# Main.net
KiCad netlist of a schematic drawn in Altium Designer
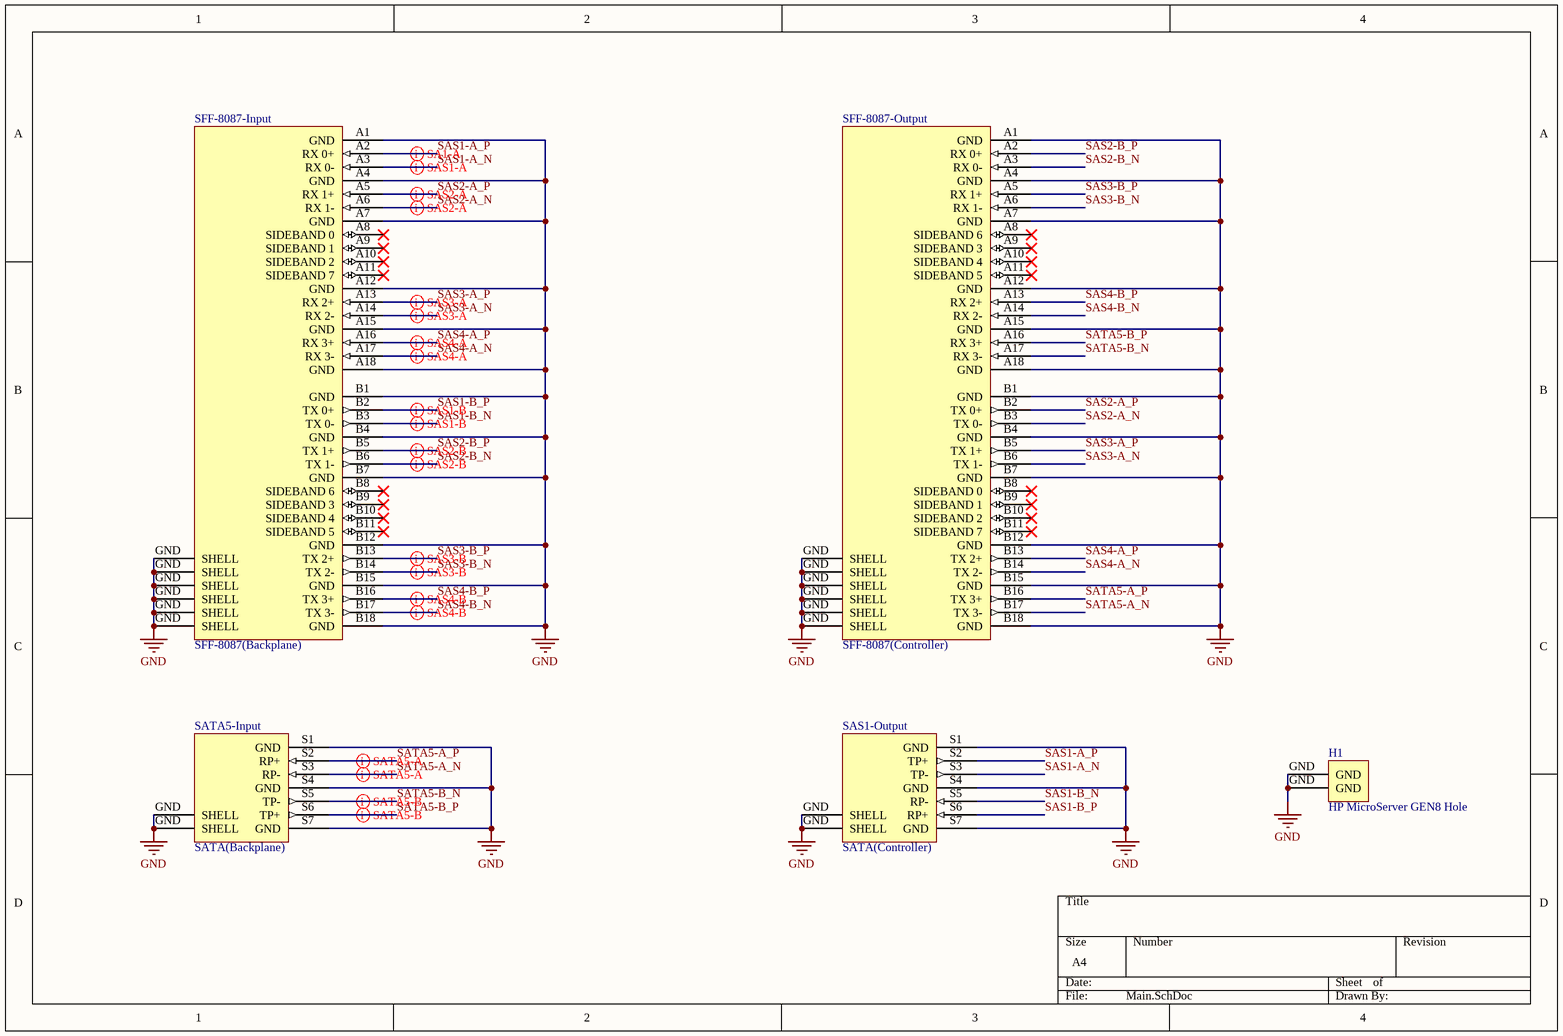
[diagram p0: Main.SchDoc]

(export (version "E")
  (design (tool "Eeschema 10.0.6"))
  (components
    (comp (ref "H1")
      (value "HP MicroServer GEN8 Hole")
      (footprint "GEN8-HDD-Backplane-Hole")
      (libsource (lib "Common") (part "HP MicroServer GEN8 Hole"))
    )
    (comp (ref "SAS1-Output")
      (value "SATA(Controller)")
      (footprint "MOLEX SATA (47080-4001)")
      (libsource (lib "Common") (part "SATA(Controller)"))
    )
    (comp (ref "SATA5-Input")
      (value "SATA(Backplane)")
      (footprint "MOLEX SATA (47080-4001)")
      (libsource (lib "Common") (part "SATA(Backplane)"))
    )
    (comp (ref "SFF-8087-Input")
      (value "SFF-8087(Backplane)")
      (footprint "Molex SFF-8087 (75783-0140)")
      (libsource (lib "Common") (part "SFF-8087(Backplane)"))
    )
    (comp (ref "SFF-8087-Output")
      (value "SFF-8087(Controller)")
      (footprint "Molex SFF-8087 (75783-0140)")
      (libsource (lib "Common") (part "SFF-8087(Controller)"))
    )
  )
  (nets
    (net (code "1") (name "/SAS1-A_N") (class "Default")
      (node (ref "SAS1-Output") (pin "S3") (pinfunction "TP-_S3") (pintype "output"))
      (node (ref "SFF-8087-Input") (pin "A3") (pinfunction "RX_0-_A3") (pintype "input"))
    )
    (net (code "2") (name "/SAS1-A_P") (class "Default")
      (node (ref "SAS1-Output") (pin "S2") (pinfunction "TP+_S2") (pintype "output"))
      (node (ref "SFF-8087-Input") (pin "A2") (pinfunction "RX_0+_A2") (pintype "input"))
    )
    (net (code "3") (name "/SAS1-B_N") (class "Default")
      (node (ref "SAS1-Output") (pin "S5") (pinfunction "RP-_S5") (pintype "input"))
      (node (ref "SFF-8087-Input") (pin "B3") (pinfunction "TX_0-_B3") (pintype "output"))
    )
    (net (code "4") (name "/SAS1-B_P") (class "Default")
      (node (ref "SAS1-Output") (pin "S6") (pinfunction "RP+_S6") (pintype "input"))
      (node (ref "SFF-8087-Input") (pin "B2") (pinfunction "TX_0+_B2") (pintype "output"))
    )
    (net (code "5") (name "/SAS2-A_N") (class "Default")
      (node (ref "SFF-8087-Input") (pin "A6") (pinfunction "RX_1-_A6") (pintype "input"))
      (node (ref "SFF-8087-Output") (pin "B3") (pinfunction "TX_0-_B3") (pintype "output"))
    )
    (net (code "6") (name "/SAS2-A_P") (class "Default")
      (node (ref "SFF-8087-Input") (pin "A5") (pinfunction "RX_1+_A5") (pintype "input"))
      (node (ref "SFF-8087-Output") (pin "B2") (pinfunction "TX_0+_B2") (pintype "output"))
    )
    (net (code "7") (name "/SAS2-B_N") (class "Default")
      (node (ref "SFF-8087-Input") (pin "B6") (pinfunction "TX_1-_B6") (pintype "output"))
      (node (ref "SFF-8087-Output") (pin "A3") (pinfunction "RX_0-_A3") (pintype "input"))
    )
    (net (code "8") (name "/SAS2-B_P") (class "Default")
      (node (ref "SFF-8087-Input") (pin "B5") (pinfunction "TX_1+_B5") (pintype "output"))
      (node (ref "SFF-8087-Output") (pin "A2") (pinfunction "RX_0+_A2") (pintype "input"))
    )
    (net (code "9") (name "/SAS3-A_N") (class "Default")
      (node (ref "SFF-8087-Input") (pin "A14") (pinfunction "RX_2-_A14") (pintype "input"))
      (node (ref "SFF-8087-Output") (pin "B6") (pinfunction "TX_1-_B6") (pintype "output"))
    )
    (net (code "10") (name "/SAS3-A_P") (class "Default")
      (node (ref "SFF-8087-Input") (pin "A13") (pinfunction "RX_2+_A13") (pintype "input"))
      (node (ref "SFF-8087-Output") (pin "B5") (pinfunction "TX_1+_B5") (pintype "output"))
    )
    (net (code "11") (name "/SAS3-B_N") (class "Default")
      (node (ref "SFF-8087-Input") (pin "B14") (pinfunction "TX_2-_B14") (pintype "output"))
      (node (ref "SFF-8087-Output") (pin "A6") (pinfunction "RX_1-_A6") (pintype "input"))
    )
    (net (code "12") (name "/SAS3-B_P") (class "Default")
      (node (ref "SFF-8087-Input") (pin "B13") (pinfunction "TX_2+_B13") (pintype "output"))
      (node (ref "SFF-8087-Output") (pin "A5") (pinfunction "RX_1+_A5") (pintype "input"))
    )
    (net (code "13") (name "/SAS4-A_N") (class "Default")
      (node (ref "SFF-8087-Input") (pin "A17") (pinfunction "RX_3-_A17") (pintype "input"))
      (node (ref "SFF-8087-Output") (pin "B14") (pinfunction "TX_2-_B14") (pintype "output"))
    )
    (net (code "14") (name "/SAS4-A_P") (class "Default")
      (node (ref "SFF-8087-Input") (pin "A16") (pinfunction "RX_3+_A16") (pintype "input"))
      (node (ref "SFF-8087-Output") (pin "B13") (pinfunction "TX_2+_B13") (pintype "output"))
    )
    (net (code "15") (name "/SAS4-B_N") (class "Default")
      (node (ref "SFF-8087-Input") (pin "B17") (pinfunction "TX_3-_B17") (pintype "output"))
      (node (ref "SFF-8087-Output") (pin "A14") (pinfunction "RX_2-_A14") (pintype "input"))
    )
    (net (code "16") (name "/SAS4-B_P") (class "Default")
      (node (ref "SFF-8087-Input") (pin "B16") (pinfunction "TX_3+_B16") (pintype "output"))
      (node (ref "SFF-8087-Output") (pin "A13") (pinfunction "RX_2+_A13") (pintype "input"))
    )
    (net (code "17") (name "/SATA5-A_N") (class "Default")
      (node (ref "SATA5-Input") (pin "S3") (pinfunction "RP-_S3") (pintype "input"))
      (node (ref "SFF-8087-Output") (pin "B17") (pinfunction "TX_3-_B17") (pintype "output"))
    )
    (net (code "18") (name "/SATA5-A_P") (class "Default")
      (node (ref "SATA5-Input") (pin "S2") (pinfunction "RP+_S2") (pintype "input"))
      (node (ref "SFF-8087-Output") (pin "B16") (pinfunction "TX_3+_B16") (pintype "output"))
    )
    (net (code "19") (name "/SATA5-B_N") (class "Default")
      (node (ref "SATA5-Input") (pin "S5") (pinfunction "TP-_S5") (pintype "output"))
      (node (ref "SFF-8087-Output") (pin "A17") (pinfunction "RX_3-_A17") (pintype "input"))
    )
    (net (code "20") (name "/SATA5-B_P") (class "Default")
      (node (ref "SATA5-Input") (pin "S6") (pinfunction "TP+_S6") (pintype "output"))
      (node (ref "SFF-8087-Output") (pin "A16") (pinfunction "RX_3+_A16") (pintype "input"))
    )
    (net (code "21") (name "GND") (class "Default")
      (node (ref "H1") (pin "GND") (pinfunction "GND_GND") (pintype "passive"))
      (node (ref "SAS1-Output") (pin "GND") (pinfunction "SHELL_GND") (pintype "passive"))
      (node (ref "SAS1-Output") (pin "S1") (pinfunction "GND_S1") (pintype "passive"))
      (node (ref "SAS1-Output") (pin "S4") (pinfunction "GND_S4") (pintype "passive"))
      (node (ref "SAS1-Output") (pin "S7") (pinfunction "GND_S7") (pintype "passive"))
      (node (ref "SATA5-Input") (pin "GND") (pinfunction "SHELL_GND") (pintype "passive"))
      (node (ref "SATA5-Input") (pin "S1") (pinfunction "GND_S1") (pintype "passive"))
      (node (ref "SATA5-Input") (pin "S4") (pinfunction "GND_S4") (pintype "passive"))
      (node (ref "SATA5-Input") (pin "S7") (pinfunction "GND_S7") (pintype "passive"))
      (node (ref "SFF-8087-Input") (pin "A1") (pinfunction "GND_A1") (pintype "passive"))
      (node (ref "SFF-8087-Input") (pin "A12") (pinfunction "GND_A12") (pintype "passive"))
      (node (ref "SFF-8087-Input") (pin "A15") (pinfunction "GND_A15") (pintype "passive"))
      (node (ref "SFF-8087-Input") (pin "A18") (pinfunction "GND_A18") (pintype "passive"))
      (node (ref "SFF-8087-Input") (pin "A4") (pinfunction "GND_A4") (pintype "passive"))
      (node (ref "SFF-8087-Input") (pin "A7") (pinfunction "GND_A7") (pintype "passive"))
      (node (ref "SFF-8087-Input") (pin "B1") (pinfunction "GND_B1") (pintype "passive"))
      (node (ref "SFF-8087-Input") (pin "B12") (pinfunction "GND_B12") (pintype "passive"))
      (node (ref "SFF-8087-Input") (pin "B15") (pinfunction "GND_B15") (pintype "passive"))
      (node (ref "SFF-8087-Input") (pin "B18") (pinfunction "GND_B18") (pintype "passive"))
      (node (ref "SFF-8087-Input") (pin "B4") (pinfunction "GND_B4") (pintype "passive"))
      (node (ref "SFF-8087-Input") (pin "B7") (pinfunction "GND_B7") (pintype "passive"))
      (node (ref "SFF-8087-Input") (pin "GND") (pinfunction "SHELL_GND") (pintype "passive"))
      (node (ref "SFF-8087-Output") (pin "A1") (pinfunction "GND_A1") (pintype "passive"))
      (node (ref "SFF-8087-Output") (pin "A12") (pinfunction "GND_A12") (pintype "passive"))
      (node (ref "SFF-8087-Output") (pin "A15") (pinfunction "GND_A15") (pintype "passive"))
      (node (ref "SFF-8087-Output") (pin "A18") (pinfunction "GND_A18") (pintype "passive"))
      (node (ref "SFF-8087-Output") (pin "A4") (pinfunction "GND_A4") (pintype "passive"))
      (node (ref "SFF-8087-Output") (pin "A7") (pinfunction "GND_A7") (pintype "passive"))
      (node (ref "SFF-8087-Output") (pin "B1") (pinfunction "GND_B1") (pintype "passive"))
      (node (ref "SFF-8087-Output") (pin "B12") (pinfunction "GND_B12") (pintype "passive"))
      (node (ref "SFF-8087-Output") (pin "B15") (pinfunction "GND_B15") (pintype "passive"))
      (node (ref "SFF-8087-Output") (pin "B18") (pinfunction "GND_B18") (pintype "passive"))
      (node (ref "SFF-8087-Output") (pin "B4") (pinfunction "GND_B4") (pintype "passive"))
      (node (ref "SFF-8087-Output") (pin "B7") (pinfunction "GND_B7") (pintype "passive"))
      (node (ref "SFF-8087-Output") (pin "GND") (pinfunction "SHELL_GND") (pintype "passive"))
    )
    (net (code "22") (name "unconnected-(SFF-8087-Input-SIDEBAND_0-PadA8)") (class "Default")
      (node (ref "SFF-8087-Input") (pin "A8") (pinfunction "SIDEBAND_0_A8") (pintype "bidirectional+no_connect"))
    )
    (net (code "23") (name "unconnected-(SFF-8087-Input-SIDEBAND_1-PadA9)") (class "Default")
      (node (ref "SFF-8087-Input") (pin "A9") (pinfunction "SIDEBAND_1_A9") (pintype "bidirectional+no_connect"))
    )
    (net (code "24") (name "unconnected-(SFF-8087-Input-SIDEBAND_2-PadA10)") (class "Default")
      (node (ref "SFF-8087-Input") (pin "A10") (pinfunction "SIDEBAND_2_A10") (pintype "bidirectional+no_connect"))
    )
    (net (code "25") (name "unconnected-(SFF-8087-Input-SIDEBAND_3-PadB9)") (class "Default")
      (node (ref "SFF-8087-Input") (pin "B9") (pinfunction "SIDEBAND_3_B9") (pintype "bidirectional+no_connect"))
    )
    (net (code "26") (name "unconnected-(SFF-8087-Input-SIDEBAND_4-PadB10)") (class "Default")
      (node (ref "SFF-8087-Input") (pin "B10") (pinfunction "SIDEBAND_4_B10") (pintype "bidirectional+no_connect"))
    )
    (net (code "27") (name "unconnected-(SFF-8087-Input-SIDEBAND_5-PadB11)") (class "Default")
      (node (ref "SFF-8087-Input") (pin "B11") (pinfunction "SIDEBAND_5_B11") (pintype "bidirectional+no_connect"))
    )
    (net (code "28") (name "unconnected-(SFF-8087-Input-SIDEBAND_6-PadB8)") (class "Default")
      (node (ref "SFF-8087-Input") (pin "B8") (pinfunction "SIDEBAND_6_B8") (pintype "bidirectional+no_connect"))
    )
    (net (code "29") (name "unconnected-(SFF-8087-Input-SIDEBAND_7-PadA11)") (class "Default")
      (node (ref "SFF-8087-Input") (pin "A11") (pinfunction "SIDEBAND_7_A11") (pintype "bidirectional+no_connect"))
    )
    (net (code "30") (name "unconnected-(SFF-8087-Output-SIDEBAND_0-PadB8)") (class "Default")
      (node (ref "SFF-8087-Output") (pin "B8") (pinfunction "SIDEBAND_0_B8") (pintype "bidirectional+no_connect"))
    )
    (net (code "31") (name "unconnected-(SFF-8087-Output-SIDEBAND_1-PadB9)") (class "Default")
      (node (ref "SFF-8087-Output") (pin "B9") (pinfunction "SIDEBAND_1_B9") (pintype "bidirectional+no_connect"))
    )
    (net (code "32") (name "unconnected-(SFF-8087-Output-SIDEBAND_2-PadB10)") (class "Default")
      (node (ref "SFF-8087-Output") (pin "B10") (pinfunction "SIDEBAND_2_B10") (pintype "bidirectional+no_connect"))
    )
    (net (code "33") (name "unconnected-(SFF-8087-Output-SIDEBAND_3-PadA9)") (class "Default")
      (node (ref "SFF-8087-Output") (pin "A9") (pinfunction "SIDEBAND_3_A9") (pintype "bidirectional+no_connect"))
    )
    (net (code "34") (name "unconnected-(SFF-8087-Output-SIDEBAND_4-PadA10)") (class "Default")
      (node (ref "SFF-8087-Output") (pin "A10") (pinfunction "SIDEBAND_4_A10") (pintype "bidirectional+no_connect"))
    )
    (net (code "35") (name "unconnected-(SFF-8087-Output-SIDEBAND_5-PadA11)") (class "Default")
      (node (ref "SFF-8087-Output") (pin "A11") (pinfunction "SIDEBAND_5_A11") (pintype "bidirectional+no_connect"))
    )
    (net (code "36") (name "unconnected-(SFF-8087-Output-SIDEBAND_6-PadA8)") (class "Default")
      (node (ref "SFF-8087-Output") (pin "A8") (pinfunction "SIDEBAND_6_A8") (pintype "bidirectional+no_connect"))
    )
    (net (code "37") (name "unconnected-(SFF-8087-Output-SIDEBAND_7-PadB11)") (class "Default")
      (node (ref "SFF-8087-Output") (pin "B11") (pinfunction "SIDEBAND_7_B11") (pintype "bidirectional+no_connect"))
    )
  )
)
